# suzie_bot.net
KiCad netlist of a schematic drawn in EAGLE
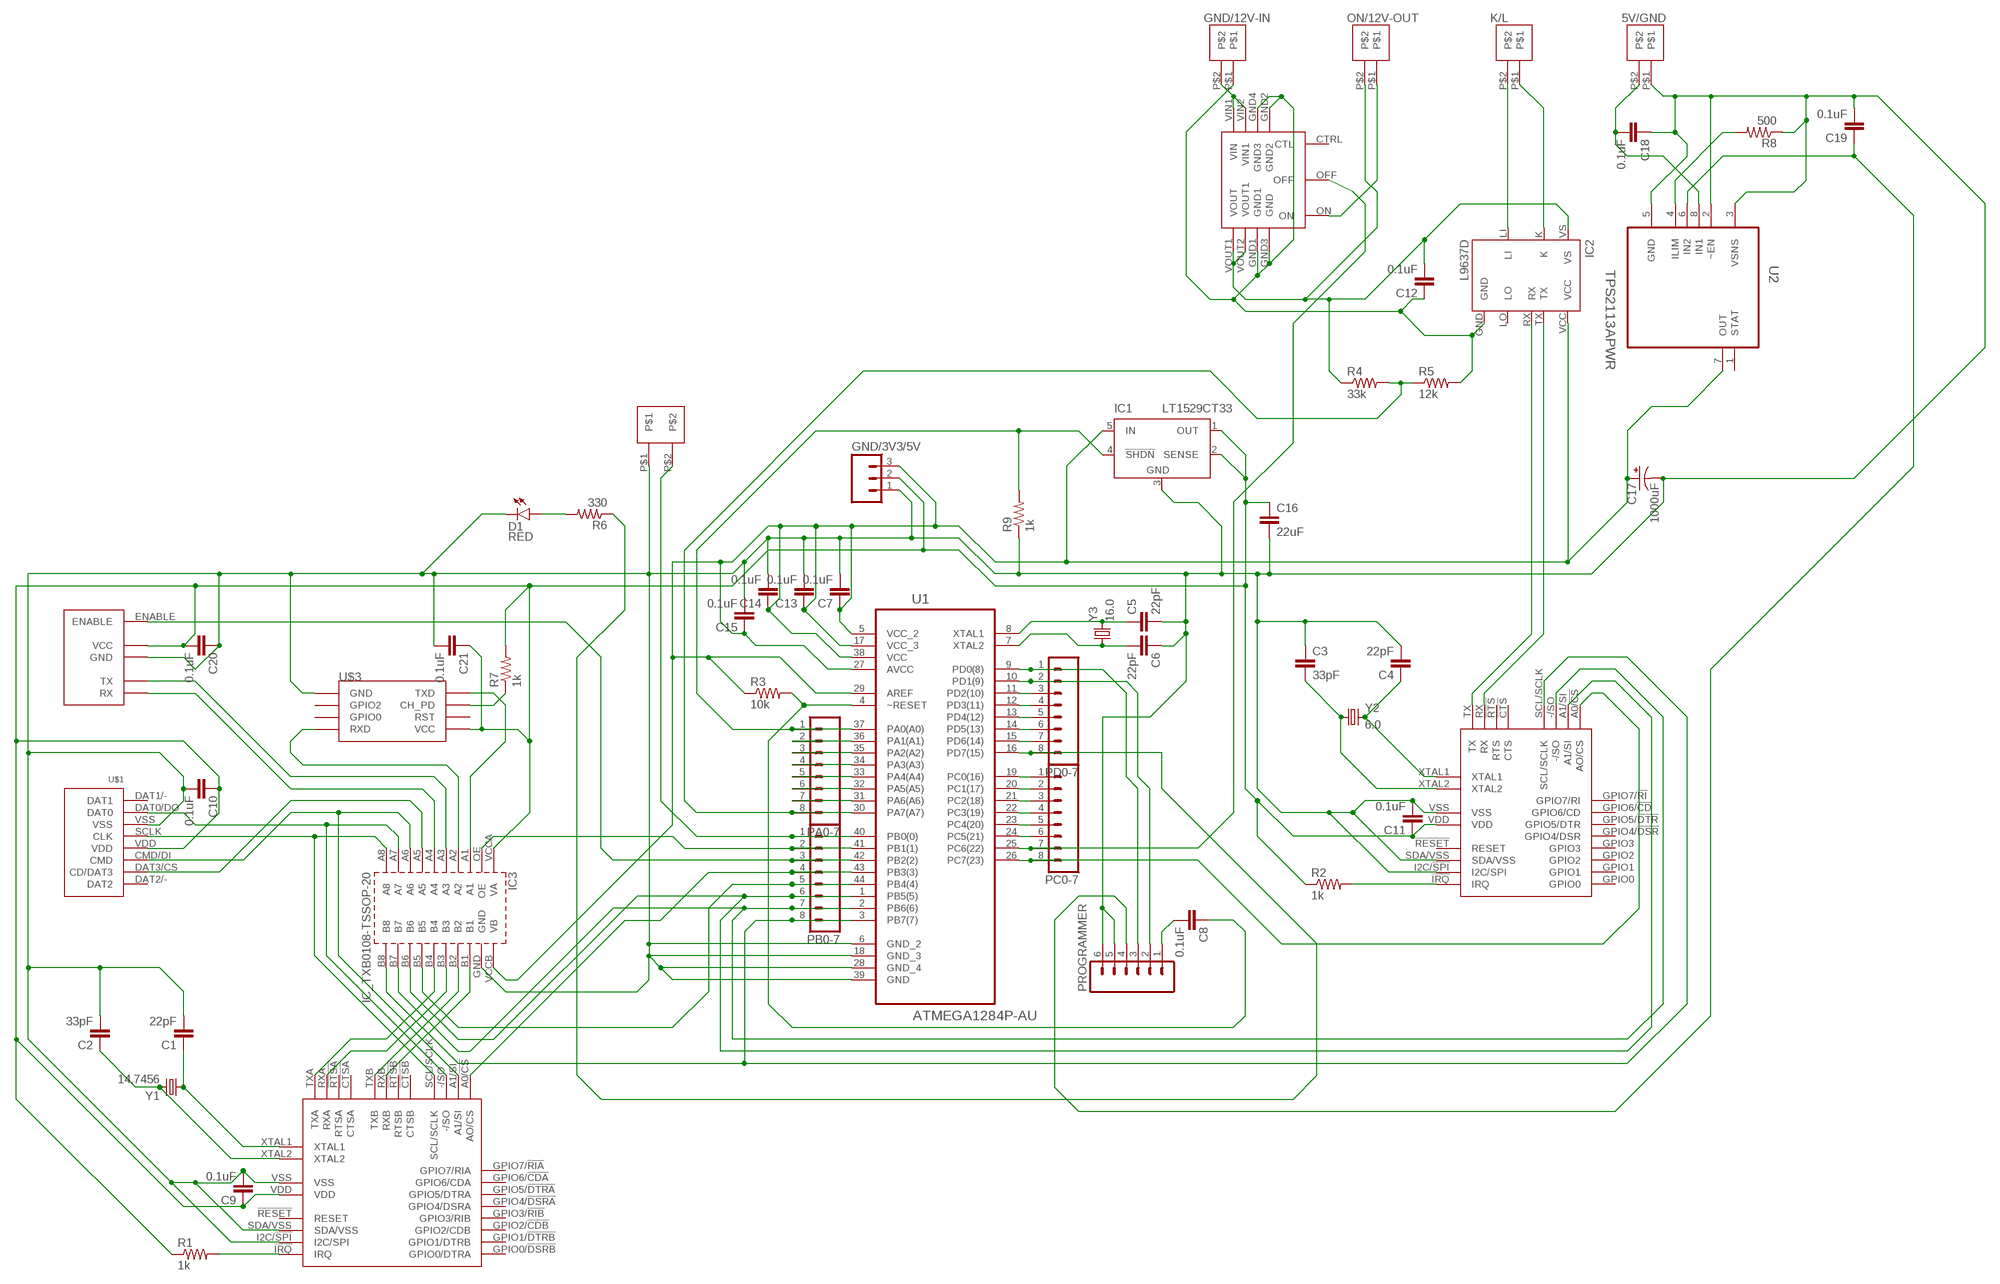
[diagram p0: schematic, sheet 1]

(export (version "E")
  (design (tool "Eeschema 10.0.6"))
  (components
    (comp (ref "5V/GND")
      (value "2-PIN-TERMINAL")
      (footprint "eagle-import:2-PIN-TERMINAL")
      (libsource (lib "eagle-import") (part "2-PIN-TERMINAL"))
    )
    (comp (ref "C1")
      (value "22pF")
      (footprint "eagle-import:0805")
      (libsource (lib "eagle-import") (part "SparkFun-Passives_CAP0805"))
    )
    (comp (ref "C2")
      (value "33pF")
      (footprint "eagle-import:0805")
      (libsource (lib "eagle-import") (part "SparkFun-Passives_CAP0805"))
    )
    (comp (ref "C3")
      (value "33pF")
      (footprint "eagle-import:0805")
      (libsource (lib "eagle-import") (part "SparkFun-Passives_CAP0805"))
    )
    (comp (ref "C4")
      (value "22pF")
      (footprint "eagle-import:0805")
      (libsource (lib "eagle-import") (part "SparkFun-Passives_CAP0805"))
    )
    (comp (ref "C5")
      (value "22pF")
      (footprint "eagle-import:0805")
      (libsource (lib "eagle-import") (part "SparkFun-Passives_CAP0805"))
    )
    (comp (ref "C6")
      (value "22pF")
      (footprint "eagle-import:0805")
      (libsource (lib "eagle-import") (part "SparkFun-Passives_CAP0805"))
    )
    (comp (ref "C7")
      (value "0.1uF")
      (footprint "eagle-import:0603-CAP")
      (libsource (lib "eagle-import") (part "CAP0603-CAP"))
    )
    (comp (ref "C8")
      (value "0.1uF")
      (footprint "eagle-import:0805")
      (libsource (lib "eagle-import") (part "SparkFun-Passives_CAP0805"))
    )
    (comp (ref "C9")
      (value "0.1uF")
      (footprint "eagle-import:0603-CAP")
      (libsource (lib "eagle-import") (part "CAP0603-CAP"))
    )
    (comp (ref "C10")
      (value "0.1uF")
      (footprint "eagle-import:0603-CAP")
      (libsource (lib "eagle-import") (part "CAP0603-CAP"))
    )
    (comp (ref "C11")
      (value "0.1uF")
      (footprint "eagle-import:0603-CAP")
      (libsource (lib "eagle-import") (part "CAP0603-CAP"))
    )
    (comp (ref "C12")
      (value "0.1uF")
      (footprint "eagle-import:0603-CAP")
      (libsource (lib "eagle-import") (part "CAP0603-CAP"))
    )
    (comp (ref "C13")
      (value "0.1uF")
      (footprint "eagle-import:0603-CAP")
      (libsource (lib "eagle-import") (part "CAP0603-CAP"))
    )
    (comp (ref "C14")
      (value "0.1uF")
      (footprint "eagle-import:0603-CAP")
      (libsource (lib "eagle-import") (part "CAP0603-CAP"))
    )
    (comp (ref "C15")
      (value "0.1uF")
      (footprint "eagle-import:0603-CAP")
      (libsource (lib "eagle-import") (part "CAP0603-CAP"))
    )
    (comp (ref "C16")
      (value "22uF")
      (footprint "eagle-import:1206")
      (libsource (lib "eagle-import") (part "CAP1206"))
    )
    (comp (ref "C17")
      (value "1000uF")
      (footprint "eagle-import:PANASONIC_G")
      (libsource (lib "eagle-import") (part "CPOL-USG"))
    )
    (comp (ref "C18")
      (value "0.1uF")
      (footprint "eagle-import:0603-CAP")
      (libsource (lib "eagle-import") (part "CAP0603-CAP"))
    )
    (comp (ref "C19")
      (value "0.1uF")
      (footprint "eagle-import:0603-CAP")
      (libsource (lib "eagle-import") (part "CAP0603-CAP"))
    )
    (comp (ref "C20")
      (value "0.1uF")
      (footprint "eagle-import:0603-CAP")
      (libsource (lib "eagle-import") (part "CAP0603-CAP"))
    )
    (comp (ref "C21")
      (value "0.1uF")
      (footprint "eagle-import:0603-CAP")
      (libsource (lib "eagle-import") (part "CAP0603-CAP"))
    )
    (comp (ref "D1")
      (value "RED")
      (footprint "eagle-import:LED5MM")
      (libsource (lib "eagle-import") (part "LED5MM"))
    )
    (comp (ref "GND/3V3/5V")
      (value "M03PTH")
      (footprint "eagle-import:1X03")
      (libsource (lib "eagle-import") (part "M03PTH"))
    )
    (comp (ref "GND/12V-IN")
      (value "2-PIN-TERMINAL")
      (footprint "eagle-import:2-PIN-TERMINAL")
      (libsource (lib "eagle-import") (part "2-PIN-TERMINAL"))
    )
    (comp (ref "IC1")
      (value "LT1529CT33")
      (footprint "eagle-import:TO220-5")
      (libsource (lib "eagle-import") (part "LT1529T"))
    )
    (comp (ref "IC2")
      (value "L9637D")
      (footprint "eagle-import:SO08")
      (libsource (lib "eagle-import") (part "L9637D"))
    )
    (comp (ref "IC3")
      (value "IC_TXB0108-TSSOP-20")
      (footprint "eagle-import:TSSOP-20")
      (libsource (lib "eagle-import") (part "IC_TXB0108-TSSOP-20"))
    )
    (comp (ref "K/L")
      (value "2-PIN-TERMINAL")
      (footprint "eagle-import:2-PIN-TERMINAL")
      (libsource (lib "eagle-import") (part "2-PIN-TERMINAL"))
    )
    (comp (ref "ON/12V-OUT")
      (value "2-PIN-TERMINAL")
      (footprint "eagle-import:2-PIN-TERMINAL")
      (libsource (lib "eagle-import") (part "2-PIN-TERMINAL"))
    )
    (comp (ref "PA0-7")
      (value "M08")
      (footprint "eagle-import:1X08_ROUND")
      (libsource (lib "eagle-import") (part "M08"))
    )
    (comp (ref "PB0-7")
      (value "M08")
      (footprint "eagle-import:1X08_ROUND")
      (libsource (lib "eagle-import") (part "M08"))
    )
    (comp (ref "PC0-7")
      (value "M08")
      (footprint "eagle-import:1X08_ROUND")
      (libsource (lib "eagle-import") (part "M08"))
    )
    (comp (ref "PD0-7")
      (value "M08")
      (footprint "eagle-import:1X08_ROUND")
      (libsource (lib "eagle-import") (part "M08"))
    )
    (comp (ref "PROGRAMMER")
      (value "M06SILK_FEMALE_PTH")
      (footprint "eagle-import:1X06")
      (libsource (lib "eagle-import") (part "M06SILK_FEMALE_PTH"))
    )
    (comp (ref "R1")
      (value "1k")
      (footprint "eagle-import:0805")
      (libsource (lib "eagle-import") (part "RESISTOR0805-RES"))
    )
    (comp (ref "R2")
      (value "1k")
      (footprint "eagle-import:0805")
      (libsource (lib "eagle-import") (part "RESISTOR0805-RES"))
    )
    (comp (ref "R3")
      (value "10k")
      (footprint "eagle-import:0805")
      (libsource (lib "eagle-import") (part "RESISTOR0805-RES"))
    )
    (comp (ref "R4")
      (value "33k")
      (footprint "eagle-import:0805")
      (libsource (lib "eagle-import") (part "RESISTOR0805-RES"))
    )
    (comp (ref "R5")
      (value "12k")
      (footprint "eagle-import:0805")
      (libsource (lib "eagle-import") (part "RESISTOR0805-RES"))
    )
    (comp (ref "R6")
      (value "330")
      (footprint "eagle-import:0805")
      (libsource (lib "eagle-import") (part "RESISTOR0805-RES"))
    )
    (comp (ref "R7")
      (value "1k")
      (footprint "eagle-import:0805")
      (libsource (lib "eagle-import") (part "RESISTOR0805-RES"))
    )
    (comp (ref "R8")
      (value "500")
      (footprint "eagle-import:0805")
      (libsource (lib "eagle-import") (part "RESISTOR0805-RES"))
    )
    (comp (ref "R9")
      (value "1k")
      (footprint "eagle-import:0805")
      (libsource (lib "eagle-import") (part "RESISTOR0805-RES"))
    )
    (comp (ref "U$1")
      (value "CON_MICROSDHINGED")
      (footprint "eagle-import:CON_MICROSD_HINGED")
      (libsource (lib "eagle-import") (part "CON_MICROSDHINGED"))
    )
    (comp (ref "U$2")
      (value "SC16IS752IPW")
      (footprint "eagle-import:TSSOP28")
      (libsource (lib "eagle-import") (part "SC16IS752IPW"))
    )
    (comp (ref "U$3")
      (value "ESP01")
      (footprint "eagle-import:ESP01")
      (libsource (lib "eagle-import") (part "ESP01"))
    )
    (comp (ref "U$4")
      (value "MINI")
      (footprint "eagle-import:MINI")
      (libsource (lib "eagle-import") (part "MINI"))
    )
    (comp (ref "U$5")
      (value "FEATHERWING")
      (footprint "eagle-import:FEATHERWING")
      (libsource (lib "eagle-import") (part "FEATHERWING"))
    )
    (comp (ref "U$7")
      (value "SC16IS750IPW")
      (footprint "eagle-import:TSSOP-24")
      (libsource (lib "eagle-import") (part "SC16IS750IPW"))
    )
    (comp (ref "U$11")
      (value "PIEZO")
      (footprint "eagle-import:17MM-PIEZO")
      (libsource (lib "eagle-import") (part "PIEZO"))
    )
    (comp (ref "U1")
      (value "ATMEGA1284P-AU")
      (footprint "eagle-import:QFP80P1200X1200X120-44N")
      (libsource (lib "eagle-import") (part "ATMEGA1284P-AU"))
    )
    (comp (ref "U2")
      (value "TPS2113APWR")
      (footprint "eagle-import:SOP65P640X120-8N")
      (libsource (lib "eagle-import") (part "TPS2113APWR"))
    )
    (comp (ref "Y1")
      (value "14.7456")
      (footprint "eagle-import:HC49US")
      (libsource (lib "eagle-import") (part "CRYSTALHC49US"))
    )
    (comp (ref "Y2")
      (value "6.0")
      (footprint "eagle-import:HC49US")
      (libsource (lib "eagle-import") (part "CRYSTALHC49US"))
    )
    (comp (ref "Y3")
      (value "16.0")
      (footprint "eagle-import:HC49US")
      (libsource (lib "eagle-import") (part "CRYSTALHC49US"))
    )
  )
  (nets
    (net (code "1") (name "Net-(C1-Pad1)") (class "Default")
      (node (ref "C1") (pin "1") (pinfunction "1_1") (pintype "passive"))
      (node (ref "U$2") (pin "XTAL1") (pinfunction "XTAL1_XTAL1") (pintype "bidirectional"))
      (node (ref "Y1") (pin "1") (pinfunction "1_1") (pintype "passive"))
    )
    (net (code "2") (name "Net-(C2-Pad1)") (class "Default")
      (node (ref "C2") (pin "1") (pinfunction "1_1") (pintype "passive"))
      (node (ref "U$2") (pin "XTAL2") (pinfunction "XTAL2_XTAL2") (pintype "bidirectional"))
      (node (ref "Y1") (pin "2") (pinfunction "2_2") (pintype "passive"))
    )
    (net (code "3") (name "Net-(C3-Pad2)") (class "Default")
      (node (ref "C3") (pin "2") (pinfunction "2_2") (pintype "passive"))
      (node (ref "U$7") (pin "XTAL2") (pinfunction "XTAL2_XTAL2") (pintype "bidirectional"))
      (node (ref "Y2") (pin "1") (pinfunction "1_1") (pintype "passive"))
    )
    (net (code "4") (name "Net-(C4-Pad1)") (class "Default")
      (node (ref "C4") (pin "1") (pinfunction "1_1") (pintype "passive"))
      (node (ref "U$7") (pin "XTAL1") (pinfunction "XTAL1_XTAL1") (pintype "bidirectional"))
      (node (ref "Y2") (pin "2") (pinfunction "2_2") (pintype "passive"))
    )
    (net (code "5") (name "Net-(C8-Pad2)") (class "Default")
      (node (ref "C8") (pin "2") (pinfunction "2_2") (pintype "passive"))
      (node (ref "PROGRAMMER") (pin "1") (pinfunction "1_1") (pintype "passive"))
    )
    (net (code "6") (name "Net-(D1-C)") (class "Default")
      (node (ref "5V/GND") (pin "P$1") (pinfunction "P$1_P$1") (pintype "bidirectional"))
      (node (ref "C1") (pin "2") (pinfunction "2_2") (pintype "passive"))
      (node (ref "C10") (pin "2") (pinfunction "2_2") (pintype "passive"))
      (node (ref "C11") (pin "2") (pinfunction "2_2") (pintype "passive"))
      (node (ref "C13") (pin "2") (pinfunction "2_2") (pintype "passive"))
      (node (ref "C14") (pin "2") (pinfunction "2_2") (pintype "passive"))
      (node (ref "C15") (pin "2") (pinfunction "2_2") (pintype "passive"))
      (node (ref "C16") (pin "2") (pinfunction "2_2") (pintype "passive"))
      (node (ref "C17") (pin "-") (pinfunction "-_-") (pintype "passive"))
      (node (ref "C18") (pin "1") (pinfunction "1_1") (pintype "passive"))
      (node (ref "C19") (pin "2") (pinfunction "2_2") (pintype "passive"))
      (node (ref "C2") (pin "2") (pinfunction "2_2") (pintype "passive"))
      (node (ref "C20") (pin "1") (pinfunction "1_1") (pintype "passive"))
      (node (ref "C21") (pin "2") (pinfunction "2_2") (pintype "passive"))
      (node (ref "C3") (pin "1") (pinfunction "1_1") (pintype "passive"))
      (node (ref "C4") (pin "2") (pinfunction "2_2") (pintype "passive"))
      (node (ref "C5") (pin "2") (pinfunction "2_2") (pintype "passive"))
      (node (ref "C6") (pin "1") (pinfunction "1_1") (pintype "passive"))
      (node (ref "C7") (pin "2") (pinfunction "2_2") (pintype "passive"))
      (node (ref "C9") (pin "2") (pinfunction "2_2") (pintype "passive"))
      (node (ref "D1") (pin "K") (pinfunction "C_K") (pintype "passive"))
      (node (ref "GND/3V3/5V") (pin "1") (pinfunction "1_1") (pintype "passive"))
      (node (ref "IC1") (pin "3") (pinfunction "GND_3") (pintype "power_in"))
      (node (ref "IC3") (pin "GND") (pinfunction "GND_GND") (pintype "bidirectional"))
      (node (ref "PROGRAMMER") (pin "5") (pinfunction "5_5") (pintype "passive"))
      (node (ref "PROGRAMMER") (pin "6") (pinfunction "6_6") (pintype "passive"))
      (node (ref "R8") (pin "1") (pinfunction "1_1") (pintype "passive"))
      (node (ref "R9") (pin "1") (pinfunction "1_1") (pintype "passive"))
      (node (ref "U$1") (pin "VSS") (pinfunction "VSS_VSS") (pintype "bidirectional"))
      (node (ref "U$11") (pin "P$1") (pinfunction "P$1_P$1") (pintype "bidirectional"))
      (node (ref "U$2") (pin "I2C/!SPI") (pinfunction "I2C/SPI_I2C/!SPI") (pintype "bidirectional"))
      (node (ref "U$2") (pin "SDA/VSS") (pinfunction "SDA/VSS_SDA/VSS") (pintype "bidirectional"))
      (node (ref "U$2") (pin "VSS") (pinfunction "VSS_VSS") (pintype "bidirectional"))
      (node (ref "U$3") (pin "GND") (pinfunction "GND_GND") (pintype "bidirectional"))
      (node (ref "U$5") (pin "GND") (pinfunction "GND_GND") (pintype "bidirectional"))
      (node (ref "U$7") (pin "I2C/!SPI") (pinfunction "I2C/SPI_I2C/!SPI") (pintype "bidirectional"))
      (node (ref "U$7") (pin "SDA/VSS") (pinfunction "SDA/VSS_SDA/VSS") (pintype "bidirectional"))
      (node (ref "U$7") (pin "VSS") (pinfunction "VSS_VSS") (pintype "bidirectional"))
      (node (ref "U1") (pin "18") (pinfunction "GND_3_18") (pintype "passive"))
      (node (ref "U1") (pin "28") (pinfunction "GND_4_28") (pintype "passive"))
      (node (ref "U1") (pin "39") (pinfunction "GND_39") (pintype "passive"))
      (node (ref "U1") (pin "6") (pinfunction "GND_2_6") (pintype "passive"))
      (node (ref "U2") (pin "2") (pinfunction "~{EN}_2") (pintype "input"))
      (node (ref "U2") (pin "3") (pinfunction "VSNS_3") (pintype "power_in"))
      (node (ref "U2") (pin "5") (pinfunction "GND_5") (pintype "passive"))
    )
    (net (code "7") (name "Net-(D1-PadA)") (class "Default")
      (node (ref "D1") (pin "A") (pinfunction "A_A") (pintype "passive"))
      (node (ref "R6") (pin "2") (pinfunction "2_2") (pintype "passive"))
    )
    (net (code "8") (name "Net-(IC1-IN)") (class "Default")
      (node (ref "C13") (pin "1") (pinfunction "1_1") (pintype "passive"))
      (node (ref "C14") (pin "1") (pinfunction "1_1") (pintype "passive"))
      (node (ref "C15") (pin "1") (pinfunction "1_1") (pintype "passive"))
      (node (ref "C17") (pin "+") (pinfunction "+_+") (pintype "passive"))
      (node (ref "C7") (pin "1") (pinfunction "1_1") (pintype "passive"))
      (node (ref "GND/3V3/5V") (pin "3") (pinfunction "3_3") (pintype "passive"))
      (node (ref "IC1") (pin "5") (pinfunction "IN_5") (pintype "input"))
      (node (ref "IC2") (pin "VCC") (pinfunction "VCC_VCC") (pintype "power_in"))
      (node (ref "IC3") (pin "VCCB") (pinfunction "VB_VCCB") (pintype "bidirectional"))
      (node (ref "R3") (pin "1") (pinfunction "1_1") (pintype "passive"))
      (node (ref "U1") (pin "17") (pinfunction "VCC_3_17") (pintype "power_in"))
      (node (ref "U1") (pin "27") (pinfunction "AVCC_27") (pintype "power_in"))
      (node (ref "U1") (pin "29") (pinfunction "AREF_29") (pintype "input"))
      (node (ref "U1") (pin "38") (pinfunction "VCC_38") (pintype "power_in"))
      (node (ref "U1") (pin "5") (pinfunction "VCC_2_5") (pintype "power_in"))
      (node (ref "U2") (pin "7") (pinfunction "OUT_7") (pintype "output"))
    )
    (net (code "9") (name "Net-(IC1-OUT)") (class "Default")
      (node (ref "C10") (pin "1") (pinfunction "1_1") (pintype "passive"))
      (node (ref "C11") (pin "1") (pinfunction "1_1") (pintype "passive"))
      (node (ref "C16") (pin "1") (pinfunction "1_1") (pintype "passive"))
      (node (ref "C20") (pin "2") (pinfunction "2_2") (pintype "passive"))
      (node (ref "C21") (pin "1") (pinfunction "1_1") (pintype "passive"))
      (node (ref "C9") (pin "1") (pinfunction "1_1") (pintype "passive"))
      (node (ref "GND/3V3/5V") (pin "2") (pinfunction "2_2") (pintype "passive"))
      (node (ref "IC1") (pin "1") (pinfunction "OUT_1") (pintype "output"))
      (node (ref "IC1") (pin "2") (pinfunction "SENSE_2") (pintype "input"))
      (node (ref "IC3") (pin "VCCA") (pinfunction "VA_VCCA") (pintype "bidirectional"))
      (node (ref "R1") (pin "1") (pinfunction "1_1") (pintype "passive"))
      (node (ref "R2") (pin "1") (pinfunction "1_1") (pintype "passive"))
      (node (ref "R7") (pin "2") (pinfunction "2_2") (pintype "passive"))
      (node (ref "U$1") (pin "VDD") (pinfunction "VDD_VDD") (pintype "bidirectional"))
      (node (ref "U$2") (pin "VDD") (pinfunction "VDD_VDD") (pintype "bidirectional"))
      (node (ref "U$3") (pin "VCC") (pinfunction "VCC_VCC") (pintype "bidirectional"))
      (node (ref "U$5") (pin "VCC") (pinfunction "VCC_VCC") (pintype "bidirectional"))
      (node (ref "U$7") (pin "VDD") (pinfunction "VDD_VDD") (pintype "bidirectional"))
    )
    (net (code "10") (name "Net-(IC1-~{SHDN})") (class "Default")
      (node (ref "IC1") (pin "4") (pinfunction "~{SHDN}_4") (pintype "input"))
      (node (ref "PA0-7") (pin "1") (pinfunction "1_1") (pintype "passive"))
      (node (ref "R9") (pin "2") (pinfunction "2_2") (pintype "passive"))
      (node (ref "U1") (pin "37") (pinfunction "PA0(A0)_37") (pintype "bidirectional"))
    )
    (net (code "11") (name "Net-(IC2-PadK)") (class "Default")
      (node (ref "IC2") (pin "K") (pinfunction "K_K") (pintype "input"))
      (node (ref "K/L") (pin "P$1") (pinfunction "P$1_P$1") (pintype "bidirectional"))
    )
    (net (code "12") (name "Net-(IC2-PadLI)") (class "Default")
      (node (ref "IC2") (pin "LI") (pinfunction "LI_LI") (pintype "input"))
      (node (ref "K/L") (pin "P$2") (pinfunction "P$2_P$2") (pintype "bidirectional"))
    )
    (net (code "13") (name "Net-(IC2-PadRX)") (class "Default")
      (node (ref "IC2") (pin "RX") (pinfunction "RX_RX") (pintype "output"))
      (node (ref "U$7") (pin "TX") (pinfunction "TX_TX") (pintype "bidirectional"))
    )
    (net (code "14") (name "Net-(IC2-PadTX)") (class "Default")
      (node (ref "IC2") (pin "TX") (pinfunction "TX_TX") (pintype "input"))
      (node (ref "U$7") (pin "RX") (pinfunction "RX_RX") (pintype "bidirectional"))
    )
    (net (code "15") (name "Net-(IC3-PadB1)") (class "Default")
      (node (ref "IC3") (pin "B1") (pinfunction "B1_B1") (pintype "bidirectional"))
      (node (ref "U$2") (pin "RXB") (pinfunction "RXB_RXB") (pintype "bidirectional"))
    )
    (net (code "16") (name "Net-(IC3-PadB2)") (class "Default")
      (node (ref "IC3") (pin "B2") (pinfunction "B2_B2") (pintype "bidirectional"))
      (node (ref "U$2") (pin "TXB") (pinfunction "TXB_TXB") (pintype "bidirectional"))
    )
    (net (code "17") (name "Net-(IC3-PadB3)") (class "Default")
      (node (ref "IC3") (pin "B3") (pinfunction "B3_B3") (pintype "bidirectional"))
      (node (ref "U$2") (pin "RXA") (pinfunction "RXA_RXA") (pintype "bidirectional"))
    )
    (net (code "18") (name "Net-(IC3-PadB4)") (class "Default")
      (node (ref "IC3") (pin "B4") (pinfunction "B4_B4") (pintype "bidirectional"))
      (node (ref "U$2") (pin "TXA") (pinfunction "TXA_TXA") (pintype "bidirectional"))
    )
    (net (code "19") (name "Net-(ON/12V-OUT-PadP$1)") (class "Default")
      (node (ref "ON/12V-OUT") (pin "P$1") (pinfunction "P$1_P$1") (pintype "bidirectional"))
      (node (ref "U$4") (pin "ON") (pinfunction "ON_ON") (pintype "bidirectional"))
    )
    (net (code "20") (name "Net-(R7-Pad1)") (class "Default")
      (node (ref "R7") (pin "1") (pinfunction "1_1") (pintype "passive"))
      (node (ref "U$3") (pin "CH_PD") (pinfunction "CH_PD_CH_PD") (pintype "bidirectional"))
    )
    (net (code "21") (name "Net-(U$1-CD{slash}DAT3)") (class "Default")
      (node (ref "IC3") (pin "A5") (pinfunction "A5_A5") (pintype "bidirectional"))
      (node (ref "U$1") (pin "DAT3/CS") (pinfunction "CD/DAT3_DAT3/CS") (pintype "bidirectional"))
    )
    (net (code "22") (name "Net-(U$1-CLK)") (class "Default")
      (node (ref "IC3") (pin "A8") (pinfunction "A8_A8") (pintype "bidirectional"))
      (node (ref "U$1") (pin "SCLK") (pinfunction "CLK_SCLK") (pintype "bidirectional"))
      (node (ref "U$2") (pin "SCL/SCLK") (pinfunction "SCL/SCLK_SCL/SCLK") (pintype "bidirectional"))
    )
    (net (code "23") (name "Net-(U$1-CMD)") (class "Default")
      (node (ref "IC3") (pin "A6") (pinfunction "A6_A6") (pintype "bidirectional"))
      (node (ref "U$1") (pin "CMD/DI") (pinfunction "CMD_CMD/DI") (pintype "bidirectional"))
      (node (ref "U$2") (pin "A1/SI") (pinfunction "A1/SI_A1/SI") (pintype "bidirectional"))
    )
    (net (code "24") (name "Net-(U$1-DAT0)") (class "Default")
      (node (ref "IC3") (pin "A7") (pinfunction "A7_A7") (pintype "bidirectional"))
      (node (ref "U$1") (pin "DAT0/DO") (pinfunction "DAT0_DAT0/DO") (pintype "bidirectional"))
      (node (ref "U$2") (pin "-/SO") (pinfunction "-/SO_-/SO") (pintype "bidirectional"))
    )
    (net (code "25") (name "Net-(U$2-AO{slash}CS)") (class "Default")
      (node (ref "PB0-7") (pin "4") (pinfunction "4_4") (pintype "passive"))
      (node (ref "U$2") (pin "A0/!CS") (pinfunction "AO/CS_A0/!CS") (pintype "bidirectional"))
      (node (ref "U1") (pin "43") (pinfunction "PB3(3)_43") (pintype "bidirectional"))
    )
    (net (code "26") (name "Net-(U$2-IRQ)") (class "Default")
      (node (ref "R1") (pin "2") (pinfunction "2_2") (pintype "passive"))
      (node (ref "U$2") (pin "!IRQ") (pinfunction "IRQ_!IRQ") (pintype "bidirectional"))
    )
    (net (code "27") (name "Net-(U$3-RXD)") (class "Default")
      (node (ref "IC3") (pin "A2") (pinfunction "A2_A2") (pintype "bidirectional"))
      (node (ref "U$3") (pin "RX") (pinfunction "RXD_RX") (pintype "bidirectional"))
    )
    (net (code "28") (name "Net-(U$3-TXD)") (class "Default")
      (node (ref "IC3") (pin "A1") (pinfunction "A1_A1") (pintype "bidirectional"))
      (node (ref "U$3") (pin "TX") (pinfunction "TXD_TX") (pintype "bidirectional"))
    )
    (net (code "29") (name "Net-(U$4-GND)") (class "Default")
      (node (ref "C12") (pin "1") (pinfunction "1_1") (pintype "passive"))
      (node (ref "GND/12V-IN") (pin "P$1") (pinfunction "P$1_P$1") (pintype "bidirectional"))
      (node (ref "IC2") (pin "GND") (pinfunction "GND_GND") (pintype "power_in"))
      (node (ref "R5") (pin "2") (pinfunction "2_2") (pintype "passive"))
      (node (ref "U$4") (pin "GND1") (pinfunction "GND1_GND1") (pintype "bidirectional"))
      (node (ref "U$4") (pin "GND2") (pinfunction "GND2_GND2") (pintype "bidirectional"))
      (node (ref "U$4") (pin "GND3") (pinfunction "GND_GND3") (pintype "bidirectional"))
      (node (ref "U$4") (pin "GND4") (pinfunction "GND3_GND4") (pintype "bidirectional"))
    )
    (net (code "30") (name "Net-(U$4-VIN)") (class "Default")
      (node (ref "GND/12V-IN") (pin "P$2") (pinfunction "P$2_P$2") (pintype "bidirectional"))
      (node (ref "U$4") (pin "VIN1") (pinfunction "VIN_VIN1") (pintype "bidirectional"))
      (node (ref "U$4") (pin "VIN2") (pinfunction "VIN1_VIN2") (pintype "bidirectional"))
    )
    (net (code "31") (name "Net-(U$4-VOUT)") (class "Default")
      (node (ref "C12") (pin "2") (pinfunction "2_2") (pintype "passive"))
      (node (ref "IC2") (pin "VS") (pinfunction "VS_VS") (pintype "power_in"))
      (node (ref "ON/12V-OUT") (pin "P$2") (pinfunction "P$2_P$2") (pintype "bidirectional"))
      (node (ref "R4") (pin "1") (pinfunction "1_1") (pintype "passive"))
      (node (ref "U$4") (pin "VOUT1") (pinfunction "VOUT_VOUT1") (pintype "bidirectional"))
      (node (ref "U$4") (pin "VOUT2") (pinfunction "VOUT1_VOUT2") (pintype "bidirectional"))
    )
    (net (code "32") (name "Net-(U$5-RX)") (class "Default")
      (node (ref "IC3") (pin "A4") (pinfunction "A4_A4") (pintype "bidirectional"))
      (node (ref "U$5") (pin "RX-2") (pinfunction "RX_RX-2") (pintype "bidirectional"))
    )
    (net (code "33") (name "Net-(U$5-TX)") (class "Default")
      (node (ref "IC3") (pin "A3") (pinfunction "A3_A3") (pintype "bidirectional"))
      (node (ref "U$5") (pin "TX-2") (pinfunction "TX_TX-2") (pintype "bidirectional"))
    )
    (net (code "34") (name "Net-(U$7-AO{slash}CS)") (class "Default")
      (node (ref "PC0-7") (pin "8") (pinfunction "8_8") (pintype "passive"))
      (node (ref "U$7") (pin "A0/!CS") (pinfunction "AO/CS_A0/!CS") (pintype "bidirectional"))
      (node (ref "U1") (pin "26") (pinfunction "PC7(23)_26") (pintype "bidirectional"))
    )
    (net (code "35") (name "Net-(U$7-IRQ)") (class "Default")
      (node (ref "R2") (pin "2") (pinfunction "2_2") (pintype "passive"))
      (node (ref "U$7") (pin "!IRQ") (pinfunction "IRQ_!IRQ") (pintype "bidirectional"))
    )
    (net (code "36") (name "Net-(U1-PA1(A1))") (class "Default")
      (node (ref "PA0-7") (pin "2") (pinfunction "2_2") (pintype "passive"))
      (node (ref "U1") (pin "36") (pinfunction "PA1(A1)_36") (pintype "bidirectional"))
    )
    (net (code "37") (name "Net-(U1-PA2(A2))") (class "Default")
      (node (ref "PA0-7") (pin "3") (pinfunction "3_3") (pintype "passive"))
      (node (ref "U1") (pin "35") (pinfunction "PA2(A2)_35") (pintype "bidirectional"))
    )
    (net (code "38") (name "Net-(U1-PA3(A3))") (class "Default")
      (node (ref "PA0-7") (pin "4") (pinfunction "4_4") (pintype "passive"))
      (node (ref "U1") (pin "34") (pinfunction "PA3(A3)_34") (pintype "bidirectional"))
    )
    (net (code "39") (name "Net-(U1-PA4(A4))") (class "Default")
      (node (ref "PA0-7") (pin "5") (pinfunction "5_5") (pintype "passive"))
      (node (ref "U1") (pin "33") (pinfunction "PA4(A4)_33") (pintype "bidirectional"))
    )
    (net (code "40") (name "Net-(U1-PA5(A5))") (class "Default")
      (node (ref "PA0-7") (pin "6") (pinfunction "6_6") (pintype "passive"))
      (node (ref "U1") (pin "32") (pinfunction "PA5(A5)_32") (pintype "bidirectional"))
    )
    (net (code "41") (name "Net-(U1-PA6(A6))") (class "Default")
      (node (ref "PA0-7") (pin "7") (pinfunction "7_7") (pintype "passive"))
      (node (ref "U1") (pin "31") (pinfunction "PA6(A6)_31") (pintype "bidirectional"))
    )
    (net (code "42") (name "Net-(U1-PA7(A7))") (class "Default")
      (node (ref "PA0-7") (pin "8") (pinfunction "8_8") (pintype "passive"))
      (node (ref "R4") (pin "2") (pinfunction "2_2") (pintype "passive"))
      (node (ref "R5") (pin "1") (pinfunction "1_1") (pintype "passive"))
      (node (ref "U1") (pin "30") (pinfunction "PA7(A7)_30") (pintype "bidirectional"))
    )
    (net (code "43") (name "Net-(U1-PB0(0))") (class "Default")
      (node (ref "PB0-7") (pin "1") (pinfunction "1_1") (pintype "passive"))
      (node (ref "U$11") (pin "P$2") (pinfunction "P$2_P$2") (pintype "bidirectional"))
      (node (ref "U1") (pin "40") (pinfunction "PB0(0)_40") (pintype "bidirectional"))
    )
    (net (code "44") (name "Net-(U1-PB1(1))") (class "Default")
      (node (ref "IC3") (pin "OE") (pinfunction "OE_OE") (pintype "bidirectional"))
      (node (ref "PB0-7") (pin "2") (pinfunction "2_2") (pintype "passive"))
      (node (ref "U1") (pin "41") (pinfunction "PB1(1)_41") (pintype "bidirectional"))
    )
    (net (code "45") (name "Net-(U1-PB2(2))") (class "Default")
      (node (ref "PB0-7") (pin "3") (pinfunction "3_3") (pintype "passive"))
      (node (ref "U$5") (pin "ENABLE") (pinfunction "ENABLE_ENABLE") (pintype "bidirectional"))
      (node (ref "U1") (pin "42") (pinfunction "PB2(2)_42") (pintype "bidirectional"))
    )
    (net (code "46") (name "Net-(U1-PB4(4))") (class "Default")
      (node (ref "IC3") (pin "B5") (pinfunction "B5_B5") (pintype "bidirectional"))
      (node (ref "PB0-7") (pin "5") (pinfunction "5_5") (pintype "passive"))
      (node (ref "U1") (pin "44") (pinfunction "PB4(4)_44") (pintype "bidirectional"))
    )
    (net (code "47") (name "Net-(U1-PB5(5))") (class "Default")
      (node (ref "IC3") (pin "B6") (pinfunction "B6_B6") (pintype "bidirectional"))
      (node (ref "PB0-7") (pin "6") (pinfunction "6_6") (pintype "passive"))
      (node (ref "U$7") (pin "A1/SI") (pinfunction "A1/SI_A1/SI") (pintype "bidirectional"))
      (node (ref "U1") (pin "1") (pinfunction "PB5(5)_1") (pintype "bidirectional"))
    )
    (net (code "48") (name "Net-(U1-PB6(6))") (class "Default")
      (node (ref "IC3") (pin "B7") (pinfunction "B7_B7") (pintype "bidirectional"))
      (node (ref "PB0-7") (pin "7") (pinfunction "7_7") (pintype "passive"))
      (node (ref "U$7") (pin "-/SO") (pinfunction "-/SO_-/SO") (pintype "bidirectional"))
      (node (ref "U1") (pin "2") (pinfunction "PB6(6)_2") (pintype "bidirectional"))
    )
    (net (code "49") (name "Net-(U1-PB7(7))") (class "Default")
      (node (ref "IC3") (pin "B8") (pinfunction "B8_B8") (pintype "bidirectional"))
      (node (ref "PB0-7") (pin "8") (pinfunction "8_8") (pintype "passive"))
      (node (ref "U$7") (pin "SCL/SCLK") (pinfunction "SCL/SCLK_SCL/SCLK") (pintype "bidirectional"))
      (node (ref "U1") (pin "3") (pinfunction "PB7(7)_3") (pintype "bidirectional"))
    )
    (net (code "50") (name "Net-(U1-PC0(16))") (class "Default")
      (node (ref "PC0-7") (pin "1") (pinfunction "1_1") (pintype "passive"))
      (node (ref "U1") (pin "19") (pinfunction "PC0(16)_19") (pintype "bidirectional"))
    )
    (net (code "51") (name "Net-(U1-PC1(17))") (class "Default")
      (node (ref "PC0-7") (pin "2") (pinfunction "2_2") (pintype "passive"))
      (node (ref "U1") (pin "20") (pinfunction "PC1(17)_20") (pintype "bidirectional"))
    )
    (net (code "52") (name "Net-(U1-PC2(18))") (class "Default")
      (node (ref "PC0-7") (pin "3") (pinfunction "3_3") (pintype "passive"))
      (node (ref "U1") (pin "21") (pinfunction "PC2(18)_21") (pintype "bidirectional"))
    )
    (net (code "53") (name "Net-(U1-PC3(19))") (class "Default")
      (node (ref "PC0-7") (pin "4") (pinfunction "4_4") (pintype "passive"))
      (node (ref "U1") (pin "22") (pinfunction "PC3(19)_22") (pintype "bidirectional"))
    )
    (net (code "54") (name "Net-(U1-PC4(20))") (class "Default")
      (node (ref "PC0-7") (pin "5") (pinfunction "5_5") (pintype "passive"))
      (node (ref "U1") (pin "23") (pinfunction "PC4(20)_23") (pintype "bidirectional"))
    )
    (net (code "55") (name "Net-(U1-PC5(21))") (class "Default")
      (node (ref "PC0-7") (pin "6") (pinfunction "6_6") (pintype "passive"))
      (node (ref "U1") (pin "24") (pinfunction "PC5(21)_24") (pintype "bidirectional"))
    )
    (net (code "56") (name "Net-(U1-PC6(22))") (class "Default")
      (node (ref "PC0-7") (pin "7") (pinfunction "7_7") (pintype "passive"))
      (node (ref "U$4") (pin "OFF") (pinfunction "OFF_OFF") (pintype "bidirectional"))
      (node (ref "U1") (pin "25") (pinfunction "PC6(22)_25") (pintype "bidirectional"))
    )
    (net (code "57") (name "Net-(U1-PD0(8))") (class "Default")
      (node (ref "PD0-7") (pin "1") (pinfunction "1_1") (pintype "passive"))
      (node (ref "PROGRAMMER") (pin "3") (pinfunction "3_3") (pintype "passive"))
      (node (ref "U1") (pin "9") (pinfunction "PD0(8)_9") (pintype "bidirectional"))
    )
    (net (code "58") (name "Net-(U1-PD1(9))") (class "Default")
      (node (ref "PD0-7") (pin "2") (pinfunction "2_2") (pintype "passive"))
      (node (ref "PROGRAMMER") (pin "2") (pinfunction "2_2") (pintype "passive"))
      (node (ref "U1") (pin "10") (pinfunction "PD1(9)_10") (pintype "bidirectional"))
    )
    (net (code "59") (name "Net-(U1-PD2(10))") (class "Default")
      (node (ref "PD0-7") (pin "3") (pinfunction "3_3") (pintype "passive"))
      (node (ref "U1") (pin "11") (pinfunction "PD2(10)_11") (pintype "bidirectional"))
    )
    (net (code "60") (name "Net-(U1-PD3(11))") (class "Default")
      (node (ref "PD0-7") (pin "4") (pinfunction "4_4") (pintype "passive"))
      (node (ref "U1") (pin "12") (pinfunction "PD3(11)_12") (pintype "bidirectional"))
    )
    (net (code "61") (name "Net-(U1-PD4(12))") (class "Default")
      (node (ref "PD0-7") (pin "5") (pinfunction "5_5") (pintype "passive"))
      (node (ref "U1") (pin "13") (pinfunction "PD4(12)_13") (pintype "bidirectional"))
    )
    (net (code "62") (name "Net-(U1-PD5(13))") (class "Default")
      (node (ref "PD0-7") (pin "6") (pinfunction "6_6") (pintype "passive"))
      (node (ref "U1") (pin "14") (pinfunction "PD5(13)_14") (pintype "bidirectional"))
    )
    (net (code "63") (name "Net-(U1-PD6(14))") (class "Default")
      (node (ref "PD0-7") (pin "7") (pinfunction "7_7") (pintype "passive"))
      (node (ref "U1") (pin "15") (pinfunction "PD6(14)_15") (pintype "bidirectional"))
    )
    (net (code "64") (name "Net-(U1-PD7(15))") (class "Default")
      (node (ref "PD0-7") (pin "8") (pinfunction "8_8") (pintype "passive"))
      (node (ref "R6") (pin "1") (pinfunction "1_1") (pintype "passive"))
      (node (ref "U1") (pin "16") (pinfunction "PD7(15)_16") (pintype "bidirectional"))
    )
    (net (code "65") (name "Net-(U1-XTAL1)") (class "Default")
      (node (ref "C5") (pin "1") (pinfunction "1_1") (pintype "passive"))
      (node (ref "U1") (pin "8") (pinfunction "XTAL1_8") (pintype "input"))
      (node (ref "Y3") (pin "2") (pinfunction "2_2") (pintype "passive"))
    )
    (net (code "66") (name "Net-(U1-XTAL2)") (class "Default")
      (node (ref "C6") (pin "2") (pinfunction "2_2") (pintype "passive"))
      (node (ref "U1") (pin "7") (pinfunction "XTAL2_7") (pintype "output"))
      (node (ref "Y3") (pin "1") (pinfunction "1_1") (pintype "passive"))
    )
    (net (code "67") (name "Net-(U1-~{RESET})") (class "Default")
      (node (ref "C8") (pin "1") (pinfunction "1_1") (pintype "passive"))
      (node (ref "R3") (pin "2") (pinfunction "2_2") (pintype "passive"))
      (node (ref "U1") (pin "4") (pinfunction "~{RESET}_4") (pintype "input"))
    )
    (net (code "68") (name "Net-(U2-ILIM)") (class "Default")
      (node (ref "R8") (pin "2") (pinfunction "2_2") (pintype "passive"))
      (node (ref "U2") (pin "4") (pinfunction "ILIM_4") (pintype "input"))
    )
    (net (code "69") (name "Net-(U2-IN1)") (class "Default")
      (node (ref "5V/GND") (pin "P$2") (pinfunction "P$2_P$2") (pintype "bidirectional"))
      (node (ref "C18") (pin "2") (pinfunction "2_2") (pintype "passive"))
      (node (ref "U2") (pin "8") (pinfunction "IN1_8") (pintype "input"))
    )
    (net (code "70") (name "Net-(U2-IN2)") (class "Default")
      (node (ref "C19") (pin "1") (pinfunction "1_1") (pintype "passive"))
      (node (ref "PROGRAMMER") (pin "4") (pinfunction "4_4") (pintype "passive"))
      (node (ref "U2") (pin "6") (pinfunction "IN2_6") (pintype "input"))
    )
    (net (code "71") (name "unconnected-(IC2-PadLO)") (class "Default")
      (node (ref "IC2") (pin "LO") (pinfunction "LO_LO") (pintype "output"))
    )
    (net (code "72") (name "unconnected-(U$1-DAT1-PadDAT1{slash}-)") (class "Default")
      (node (ref "U$1") (pin "DAT1/-") (pinfunction "DAT1_DAT1/-") (pintype "bidirectional"))
    )
    (net (code "73") (name "unconnected-(U$1-DAT2-PadDAT2{slash}-)") (class "Default")
      (node (ref "U$1") (pin "DAT2/-") (pinfunction "DAT2_DAT2/-") (pintype "bidirectional"))
    )
    (net (code "74") (name "unconnected-(U$2-CTSA-Pad!CTSA)") (class "Default")
      (node (ref "U$2") (pin "!CTSA") (pinfunction "CTSA_!CTSA") (pintype "bidirectional"))
    )
    (net (code "75") (name "unconnected-(U$2-CTSB-Pad!CTSB)") (class "Default")
      (node (ref "U$2") (pin "!CTSB") (pinfunction "CTSB_!CTSB") (pintype "bidirectional"))
    )
    (net (code "76") (name "unconnected-(U$2-GPIO0{slash}DTRA-PadGPIO0{slash}!DSRB)") (class "Default")
      (node (ref "U$2") (pin "GPIO0/!DSRB") (pinfunction "GPIO0/DTRA_GPIO0/!DSRB") (pintype "bidirectional"))
    )
    (net (code "77") (name "unconnected-(U$2-GPIO1{slash}DTRB-PadGPIO1{slash}!DTRB)") (class "Default")
      (node (ref "U$2") (pin "GPIO1/!DTRB") (pinfunction "GPIO1/DTRB_GPIO1/!DTRB") (pintype "bidirectional"))
    )
    (net (code "78") (name "unconnected-(U$2-GPIO2{slash}CDB-PadGPIO2{slash}!CDB)") (class "Default")
      (node (ref "U$2") (pin "GPIO2/!CDB") (pinfunction "GPIO2/CDB_GPIO2/!CDB") (pintype "bidirectional"))
    )
    (net (code "79") (name "unconnected-(U$2-GPIO3{slash}RIB-PadGPIO3{slash}!RIB)") (class "Default")
      (node (ref "U$2") (pin "GPIO3/!RIB") (pinfunction "GPIO3/RIB_GPIO3/!RIB") (pintype "bidirectional"))
    )
    (net (code "80") (name "unconnected-(U$2-GPIO4{slash}DSRA-PadGPIO4{slash}!DSRA)") (class "Default")
      (node (ref "U$2") (pin "GPIO4/!DSRA") (pinfunction "GPIO4/DSRA_GPIO4/!DSRA") (pintype "bidirectional"))
    )
    (net (code "81") (name "unconnected-(U$2-GPIO5{slash}DTRA-PadGPIO5{slash}!DTRA)") (class "Default")
      (node (ref "U$2") (pin "GPIO5/!DTRA") (pinfunction "GPIO5/DTRA_GPIO5/!DTRA") (pintype "bidirectional"))
    )
    (net (code "82") (name "unconnected-(U$2-GPIO6{slash}CDA-PadGPIO6{slash}!CDA)") (class "Default")
      (node (ref "U$2") (pin "GPIO6/!CDA") (pinfunction "GPIO6/CDA_GPIO6/!CDA") (pintype "bidirectional"))
    )
    (net (code "83") (name "unconnected-(U$2-GPIO7{slash}RIA-PadGPIO7{slash}!RIA)") (class "Default")
      (node (ref "U$2") (pin "GPIO7/!RIA") (pinfunction "GPIO7/RIA_GPIO7/!RIA") (pintype "bidirectional"))
    )
    (net (code "84") (name "unconnected-(U$2-RESET-Pad!RESET)") (class "Default")
      (node (ref "U$2") (pin "!RESET") (pinfunction "RESET_!RESET") (pintype "bidirectional"))
    )
    (net (code "85") (name "unconnected-(U$2-RTSA-Pad!RTSA)") (class "Default")
      (node (ref "U$2") (pin "!RTSA") (pinfunction "RTSA_!RTSA") (pintype "bidirectional"))
    )
    (net (code "86") (name "unconnected-(U$2-RTSB-Pad!RTSB)") (class "Default")
      (node (ref "U$2") (pin "!RTSB") (pinfunction "RTSB_!RTSB") (pintype "bidirectional"))
    )
    (net (code "87") (name "unconnected-(U$3-PadGPIO0)") (class "Default")
      (node (ref "U$3") (pin "GPIO0") (pinfunction "GPIO0_GPIO0") (pintype "bidirectional"))
    )
    (net (code "88") (name "unconnected-(U$3-PadGPIO2)") (class "Default")
      (node (ref "U$3") (pin "GPIO2") (pinfunction "GPIO2_GPIO2") (pintype "bidirectional"))
    )
    (net (code "89") (name "unconnected-(U$3-PadRST)") (class "Default")
      (node (ref "U$3") (pin "RST") (pinfunction "RST_RST") (pintype "bidirectional"))
    )
    (net (code "90") (name "unconnected-(U$4-CTL-PadCTRL)") (class "Default")
      (node (ref "U$4") (pin "CTRL") (pinfunction "CTL_CTRL") (pintype "bidirectional"))
    )
    (net (code "91") (name "unconnected-(U$7-CTS-Pad!CTS)") (class "Default")
      (node (ref "U$7") (pin "!CTS") (pinfunction "CTS_!CTS") (pintype "bidirectional"))
    )
    (net (code "92") (name "unconnected-(U$7-GPIO4{slash}DSR-PadGPIO4{slash}!DSR)") (class "Default")
      (node (ref "U$7") (pin "GPIO4/!DSR") (pinfunction "GPIO4/DSR_GPIO4/!DSR") (pintype "bidirectional"))
    )
    (net (code "93") (name "unconnected-(U$7-GPIO5{slash}DTR-PadGPIO5{slash}!DTR)") (class "Default")
      (node (ref "U$7") (pin "GPIO5/!DTR") (pinfunction "GPIO5/DTR_GPIO5/!DTR") (pintype "bidirectional"))
    )
    (net (code "94") (name "unconnected-(U$7-GPIO6{slash}CD-PadGPIO6{slash}!CD)") (class "Default")
      (node (ref "U$7") (pin "GPIO6/!CD") (pinfunction "GPIO6/CD_GPIO6/!CD") (pintype "bidirectional"))
    )
    (net (code "95") (name "unconnected-(U$7-GPIO7{slash}RI-PadGPIO7{slash}!RI)") (class "Default")
      (node (ref "U$7") (pin "GPIO7/!RI") (pinfunction "GPIO7/RI_GPIO7/!RI") (pintype "bidirectional"))
    )
    (net (code "96") (name "unconnected-(U$7-PadGPIO0)") (class "Default")
      (node (ref "U$7") (pin "GPIO0") (pinfunction "GPIO0_GPIO0") (pintype "bidirectional"))
    )
    (net (code "97") (name "unconnected-(U$7-PadGPIO1)") (class "Default")
      (node (ref "U$7") (pin "GPIO1") (pinfunction "GPIO1_GPIO1") (pintype "bidirectional"))
    )
    (net (code "98") (name "unconnected-(U$7-PadGPIO2)") (class "Default")
      (node (ref "U$7") (pin "GPIO2") (pinfunction "GPIO2_GPIO2") (pintype "bidirectional"))
    )
    (net (code "99") (name "unconnected-(U$7-PadGPIO3)") (class "Default")
      (node (ref "U$7") (pin "GPIO3") (pinfunction "GPIO3_GPIO3") (pintype "bidirectional"))
    )
    (net (code "100") (name "unconnected-(U$7-RESET-Pad!RESET)") (class "Default")
      (node (ref "U$7") (pin "!RESET") (pinfunction "RESET_!RESET") (pintype "bidirectional"))
    )
    (net (code "101") (name "unconnected-(U$7-RTS-Pad!RTS)") (class "Default")
      (node (ref "U$7") (pin "!RTS") (pinfunction "RTS_!RTS") (pintype "bidirectional"))
    )
    (net (code "102") (name "unconnected-(U2-STAT-Pad1)") (class "Default")
      (node (ref "U2") (pin "1") (pinfunction "STAT_1") (pintype "output"))
    )
  )
)
